# giraffe_bosch_comma.net
KiCad netlist of a schematic drawn in EAGLE
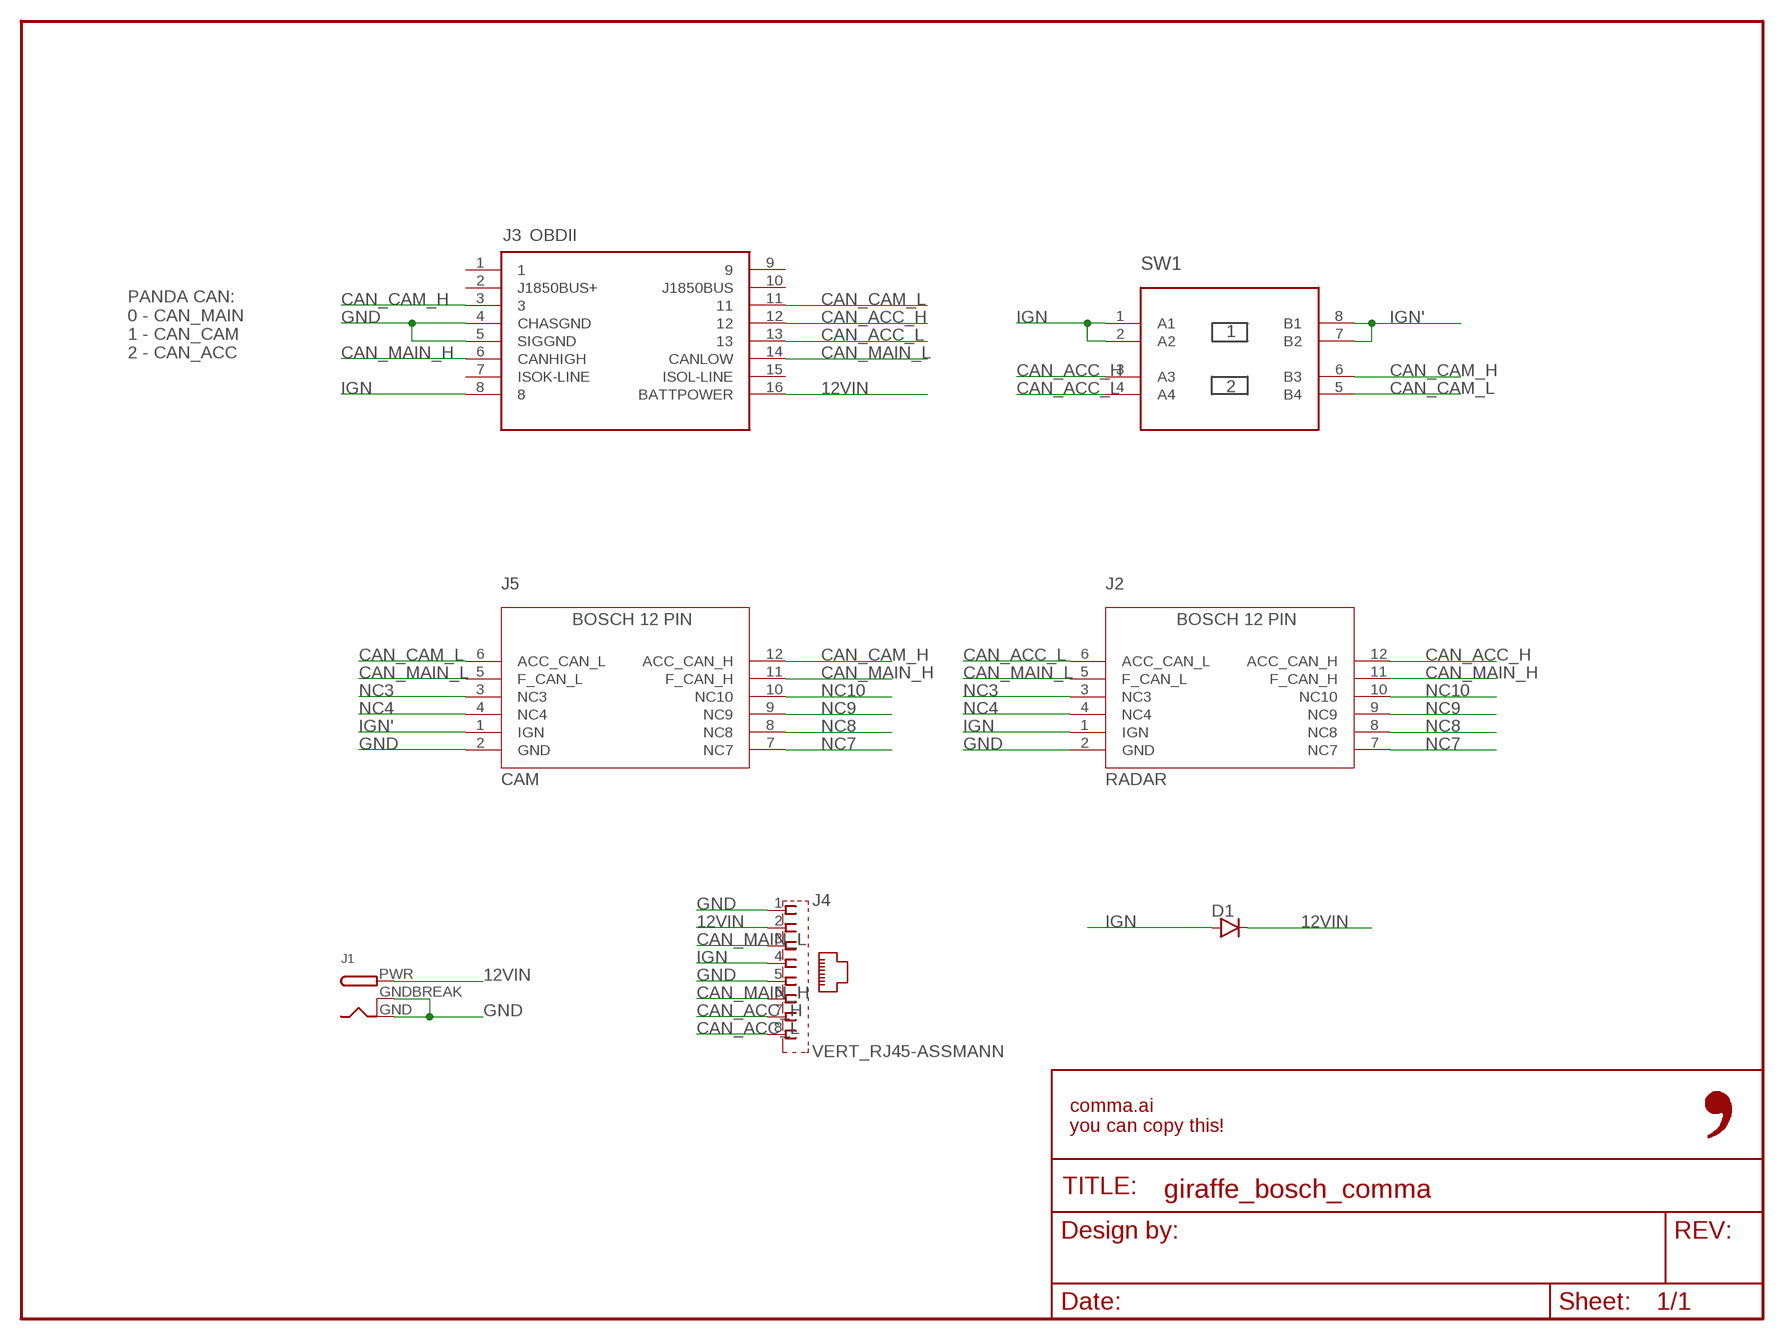
[diagram p0: schematic, sheet 1]

(export (version "E")
  (design (tool "Eeschema 10.0.6"))
  (components
    (comp (ref "D1")
      (value "DIODE-")
      (footprint "eagle-import:DO-214")
      (libsource (lib "eagle-import") (part "DIODE-"))
    )
    (comp (ref "FRAME1")
      (value "FRAME-LETTER-OPENNO_PACKAGE")
      (footprint "eagle-import:DUMMY")
      (fields (field (name "DESIGNER") "Nobody"))
      (libsource (lib "eagle-import") (part "FRAME-LETTER-OPENNO_PACKAGE"))
    )
    (comp (ref "J1")
      (value "DCBARRELPTH")
      (footprint "eagle-import:DCJACK_2MM_PTH")
      (libsource (lib "eagle-import") (part "DCBARRELPTH"))
    )
    (comp (ref "J2")
      (value "RADAR")
      (footprint "eagle-import:BOSCH_12_PIN_FEMALE")
      (libsource (lib "eagle-import") (part "BOSCH_12_PIN-F"))
    )
    (comp (ref "J3")
      (value "OBDII-FEMALE-CUT")
      (footprint "eagle-import:OBDII-FEMALE-MIDCUT")
      (libsource (lib "eagle-import") (part "OBDII-FEMALE-CUT"))
    )
    (comp (ref "J4")
      (value "VERT_RJ45-ASSMANN")
      (footprint "eagle-import:RJ45-VERT")
      (libsource (lib "eagle-import") (part "VERT_RJ45-ASSMANN"))
    )
    (comp (ref "J5")
      (value "CAM")
      (footprint "eagle-import:BOSCH_12_PIN_MALE")
      (libsource (lib "eagle-import") (part "BOSCH_12_PIN-M"))
    )
    (comp (ref "SW1")
      (value "2XDPST-CTS")
      (footprint "eagle-import:2-DPST")
      (libsource (lib "eagle-import") (part "2XDPST-CTS"))
    )
  )
  (nets
    (net (code "1") (name "/12VIN") (class "Default")
      (node (ref "D1") (pin "1") (pinfunction "C_1") (pintype "passive"))
      (node (ref "J1") (pin "PWR") (pinfunction "PWR_PWR") (pintype "power_in"))
      (node (ref "J3") (pin "16") (pinfunction "BATTPOWER_16") (pintype "bidirectional"))
      (node (ref "J4") (pin "2") (pinfunction "2_2") (pintype "passive"))
    )
    (net (code "2") (name "/CAN_ACC_H") (class "Default")
      (node (ref "J2") (pin "12") (pinfunction "ACC_CAN_H_12") (pintype "bidirectional"))
      (node (ref "J3") (pin "12") (pinfunction "12_12") (pintype "bidirectional"))
      (node (ref "J4") (pin "7") (pinfunction "7_7") (pintype "passive"))
      (node (ref "SW1") (pin "3") (pinfunction "A3_3") (pintype "bidirectional"))
    )
    (net (code "3") (name "/CAN_ACC_L") (class "Default")
      (node (ref "J2") (pin "6") (pinfunction "ACC_CAN_L_6") (pintype "bidirectional"))
      (node (ref "J3") (pin "13") (pinfunction "13_13") (pintype "bidirectional"))
      (node (ref "J4") (pin "8") (pinfunction "8_8") (pintype "passive"))
      (node (ref "SW1") (pin "4") (pinfunction "A4_4") (pintype "bidirectional"))
    )
    (net (code "4") (name "/CAN_CAM_H") (class "Default")
      (node (ref "J3") (pin "3") (pinfunction "3_3") (pintype "bidirectional"))
      (node (ref "J5") (pin "12") (pinfunction "ACC_CAN_H_12") (pintype "bidirectional"))
      (node (ref "SW1") (pin "6") (pinfunction "B3_6") (pintype "bidirectional"))
    )
    (net (code "5") (name "/CAN_CAM_L") (class "Default")
      (node (ref "J3") (pin "11") (pinfunction "11_11") (pintype "bidirectional"))
      (node (ref "J5") (pin "6") (pinfunction "ACC_CAN_L_6") (pintype "bidirectional"))
      (node (ref "SW1") (pin "5") (pinfunction "B4_5") (pintype "bidirectional"))
    )
    (net (code "6") (name "/CAN_MAIN_H") (class "Default")
      (node (ref "J2") (pin "11") (pinfunction "F_CAN_H_11") (pintype "bidirectional"))
      (node (ref "J3") (pin "6") (pinfunction "CANHIGH_6") (pintype "bidirectional"))
      (node (ref "J4") (pin "6") (pinfunction "6_6") (pintype "passive"))
      (node (ref "J5") (pin "11") (pinfunction "F_CAN_H_11") (pintype "bidirectional"))
    )
    (net (code "7") (name "/CAN_MAIN_L") (class "Default")
      (node (ref "J2") (pin "5") (pinfunction "F_CAN_L_5") (pintype "bidirectional"))
      (node (ref "J3") (pin "14") (pinfunction "CANLOW_14") (pintype "bidirectional"))
      (node (ref "J4") (pin "3") (pinfunction "3_3") (pintype "passive"))
      (node (ref "J5") (pin "5") (pinfunction "F_CAN_L_5") (pintype "bidirectional"))
    )
    (net (code "8") (name "/GND") (class "Default")
      (node (ref "J1") (pin "GND") (pinfunction "GND_GND") (pintype "power_in"))
      (node (ref "J1") (pin "GNDBREAK") (pinfunction "GNDBREAK_GNDBREAK") (pintype "power_in"))
      (node (ref "J2") (pin "2") (pinfunction "GND_2") (pintype "bidirectional"))
      (node (ref "J3") (pin "4") (pinfunction "CHASGND_4") (pintype "bidirectional"))
      (node (ref "J3") (pin "5") (pinfunction "SIGGND_5") (pintype "bidirectional"))
      (node (ref "J4") (pin "1") (pinfunction "1_1") (pintype "passive"))
      (node (ref "J4") (pin "5") (pinfunction "5_5") (pintype "passive"))
      (node (ref "J5") (pin "2") (pinfunction "GND_2") (pintype "bidirectional"))
    )
    (net (code "9") (name "/IGN") (class "Default")
      (node (ref "D1") (pin "2") (pinfunction "A_2") (pintype "passive"))
      (node (ref "J2") (pin "1") (pinfunction "IGN_1") (pintype "bidirectional"))
      (node (ref "J3") (pin "8") (pinfunction "8_8") (pintype "bidirectional"))
      (node (ref "J4") (pin "4") (pinfunction "4_4") (pintype "passive"))
      (node (ref "SW1") (pin "1") (pinfunction "A1_1") (pintype "bidirectional"))
      (node (ref "SW1") (pin "2") (pinfunction "A2_2") (pintype "bidirectional"))
    )
    (net (code "10") (name "/IGN'") (class "Default")
      (node (ref "J5") (pin "1") (pinfunction "IGN_1") (pintype "bidirectional"))
      (node (ref "SW1") (pin "7") (pinfunction "B2_7") (pintype "bidirectional"))
      (node (ref "SW1") (pin "8") (pinfunction "B1_8") (pintype "bidirectional"))
    )
    (net (code "11") (name "/NC3") (class "Default")
      (node (ref "J2") (pin "3") (pinfunction "NC3_3") (pintype "bidirectional"))
      (node (ref "J5") (pin "3") (pinfunction "NC3_3") (pintype "bidirectional"))
    )
    (net (code "12") (name "/NC4") (class "Default")
      (node (ref "J2") (pin "4") (pinfunction "NC4_4") (pintype "bidirectional"))
      (node (ref "J5") (pin "4") (pinfunction "NC4_4") (pintype "bidirectional"))
    )
    (net (code "13") (name "/NC7") (class "Default")
      (node (ref "J2") (pin "7") (pinfunction "NC7_7") (pintype "bidirectional"))
      (node (ref "J5") (pin "7") (pinfunction "NC7_7") (pintype "bidirectional"))
    )
    (net (code "14") (name "/NC8") (class "Default")
      (node (ref "J2") (pin "8") (pinfunction "NC8_8") (pintype "bidirectional"))
      (node (ref "J5") (pin "8") (pinfunction "NC8_8") (pintype "bidirectional"))
    )
    (net (code "15") (name "/NC9") (class "Default")
      (node (ref "J2") (pin "9") (pinfunction "NC9_9") (pintype "bidirectional"))
      (node (ref "J5") (pin "9") (pinfunction "NC9_9") (pintype "bidirectional"))
    )
    (net (code "16") (name "/NC10") (class "Default")
      (node (ref "J2") (pin "10") (pinfunction "NC10_10") (pintype "bidirectional"))
      (node (ref "J5") (pin "10") (pinfunction "NC10_10") (pintype "bidirectional"))
    )
    (net (code "17") (name "unconnected-(J3-ISOK-LINE-Pad7)") (class "Default")
      (node (ref "J3") (pin "7") (pinfunction "ISOK-LINE_7") (pintype "bidirectional"))
    )
    (net (code "18") (name "unconnected-(J3-ISOL-LINE-Pad15)") (class "Default")
      (node (ref "J3") (pin "15") (pinfunction "ISOL-LINE_15") (pintype "bidirectional"))
    )
    (net (code "19") (name "unconnected-(J3-J1850BUS+-Pad2)") (class "Default")
      (node (ref "J3") (pin "2") (pinfunction "J1850BUS+_2") (pintype "bidirectional"))
    )
    (net (code "20") (name "unconnected-(J3-J1850BUS-Pad10)") (class "Default")
      (node (ref "J3") (pin "10") (pinfunction "J1850BUS_10") (pintype "bidirectional"))
    )
    (net (code "21") (name "unconnected-(J3-Pad1)") (class "Default")
      (node (ref "J3") (pin "1") (pinfunction "1_1") (pintype "bidirectional"))
    )
    (net (code "22") (name "unconnected-(J3-Pad9)") (class "Default")
      (node (ref "J3") (pin "9") (pinfunction "9_9") (pintype "bidirectional"))
    )
  )
)
